# Sheet1.net
KiCad netlist of a schematic drawn in Altium Designer
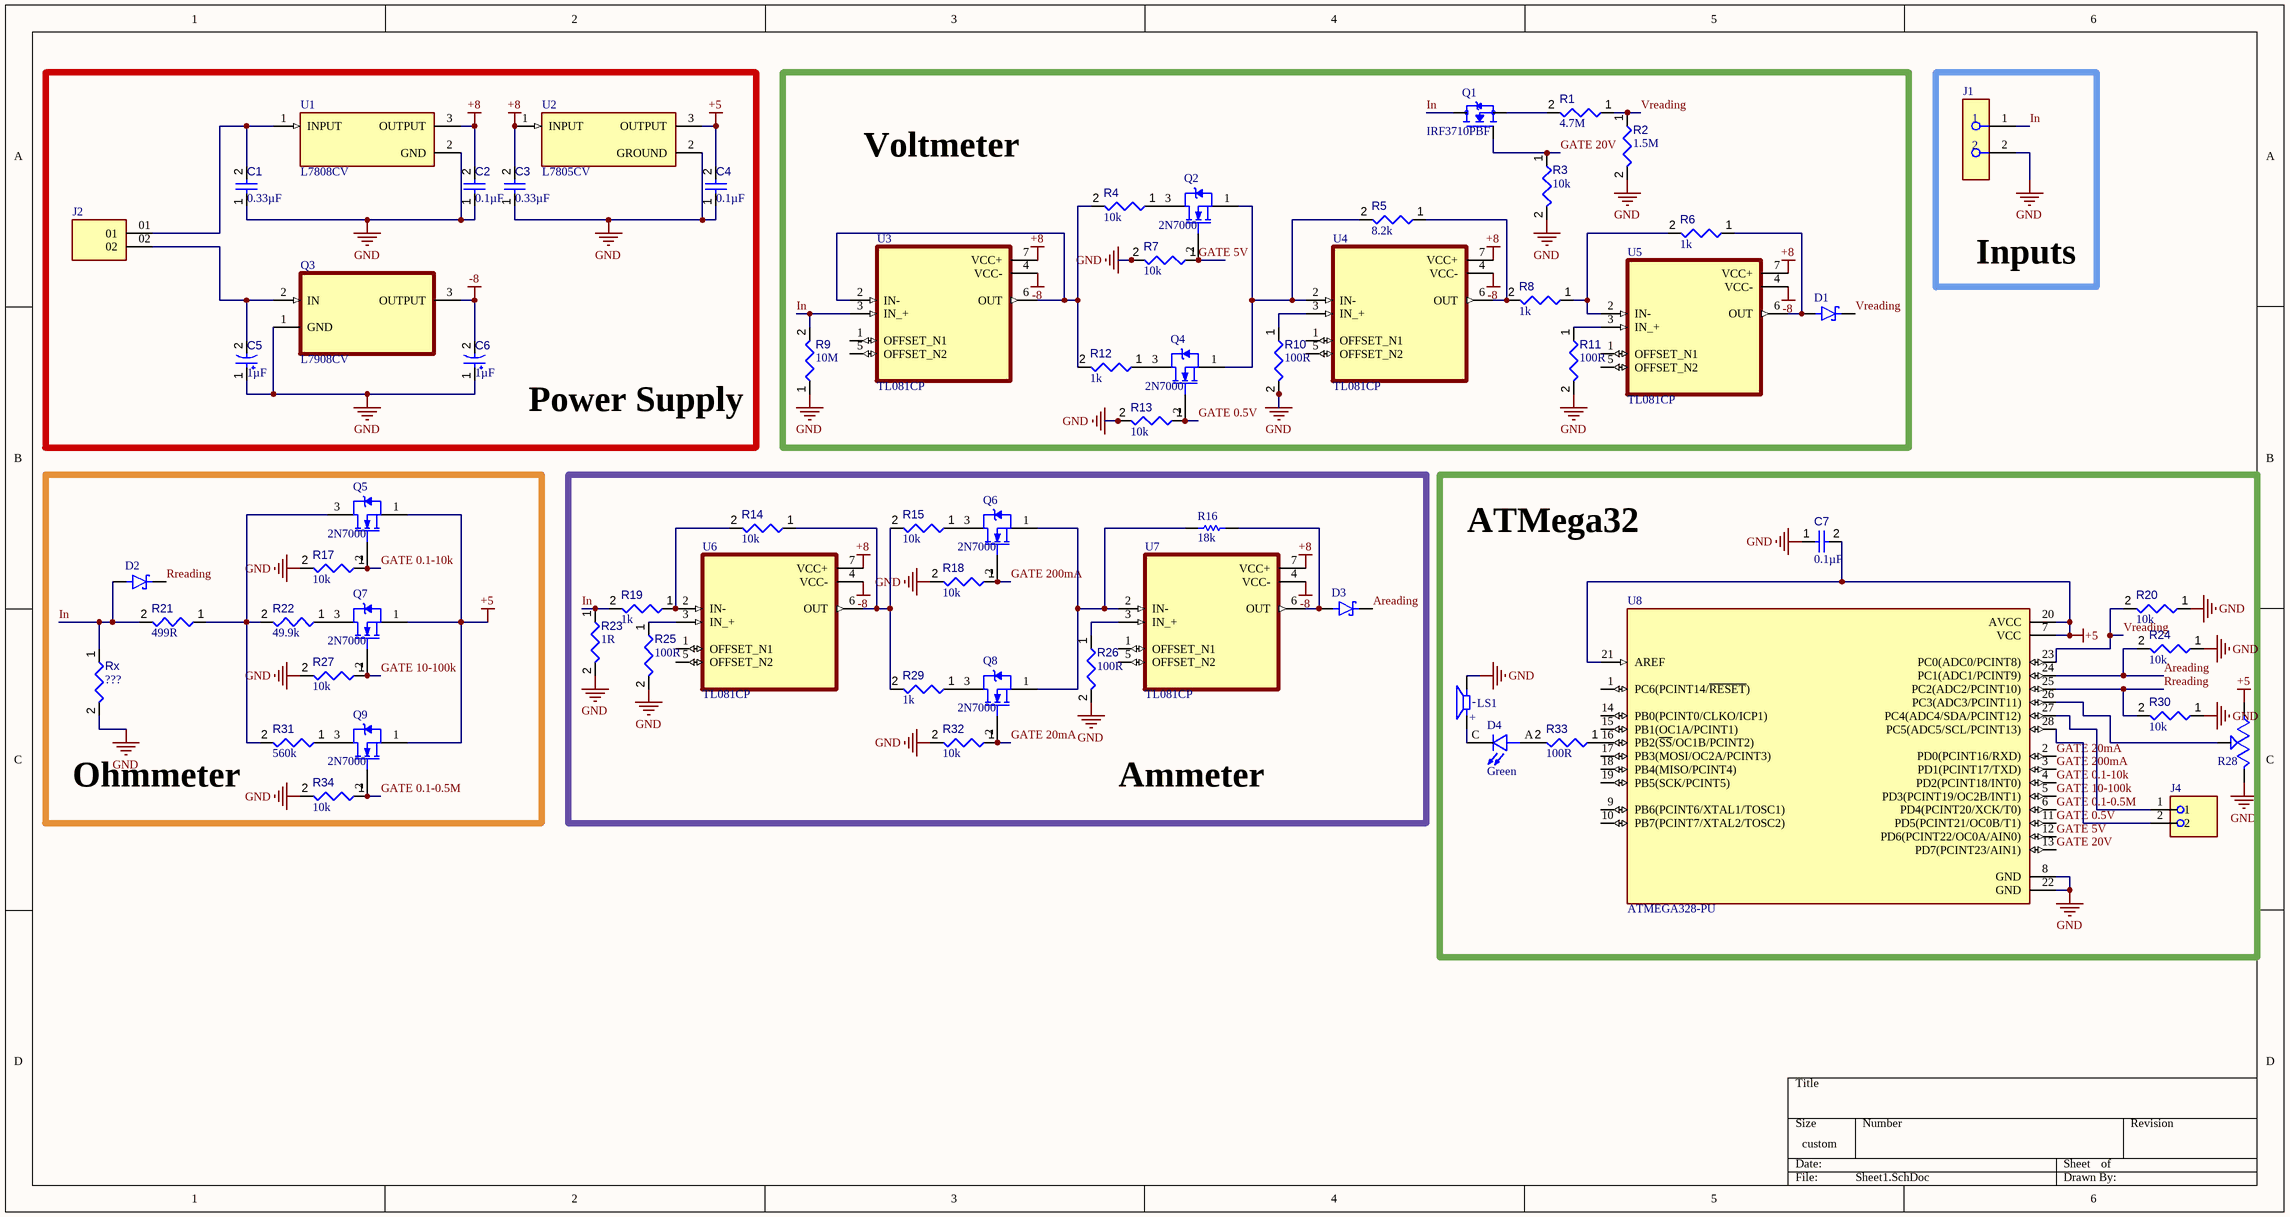
[diagram p0: Sheet1.SchDoc]

(export (version "E")
  (design (tool "Eeschema 10.0.6"))
  (components
    (comp (ref "C1")
      (value "0.33µF")
      (footprint "CAPC2013X135X45NL10T25")
      (description "Chip Capacitor, 1 uF, +/- 10%, 50 V, 0805 (2012 Metric)")
      (fields (field (name "TOLERANCE") "10%") (field (name "Comment") "Capacitor 1 uF +/- 10% 50 V 0805"))
      (libsource (lib "DMM Lab Project") (part "CAP-NP-2"))
    )
    (comp (ref "C2")
      (value "0.1µF")
      (footprint "CAPC2013X135X45NL10T25")
      (description "Chip Capacitor, 1 uF, +/- 10%, 50 V, 0805 (2012 Metric)")
      (fields (field (name "TOLERANCE") "10%") (field (name "Comment") "Capacitor 1 uF +/- 10% 50 V 0805"))
      (libsource (lib "DMM Lab Project") (part "CAP-NP-2"))
    )
    (comp (ref "C3")
      (value "0.33µF")
      (footprint "CAPC2013X135X45NL10T25")
      (description "Chip Capacitor, 1 uF, +/- 10%, 50 V, 0805 (2012 Metric)")
      (fields (field (name "TOLERANCE") "10%") (field (name "Comment") "Capacitor 1 uF +/- 10% 50 V 0805"))
      (libsource (lib "DMM Lab Project") (part "CAP-NP-2"))
    )
    (comp (ref "C4")
      (value "0.1µF")
      (footprint "CAPC2013X135X45NL10T25")
      (description "Chip Capacitor, 1 uF, +/- 10%, 50 V, 0805 (2012 Metric)")
      (fields (field (name "TOLERANCE") "10%") (field (name "Comment") "Capacitor 1 uF +/- 10% 50 V 0805"))
      (libsource (lib "DMM Lab Project") (part "CAP-NP-2"))
    )
    (comp (ref "C5")
      (value "1µF")
      (footprint "CAPPR65-350-1150X800X1250")
      (description "Aluminum Electrolytic Capacitor, 47 uF, +/- 20%, 100 V, -40 to 85 degC, 2-Pin THD, RoHS, Bulk")
      (fields (field (name "MANUFACTURER") "Panasonic") (field (name "TOLERANCE") "20%"))
      (libsource (lib "DMM Lab Project") (part "CAP-P-2"))
    )
    (comp (ref "C6")
      (value "1µF")
      (footprint "CAPPR65-350-1150X800X1250")
      (description "Aluminum Electrolytic Capacitor, 47 uF, +/- 20%, 100 V, -40 to 85 degC, 2-Pin THD, RoHS, Bulk")
      (fields (field (name "MANUFACTURER") "Panasonic") (field (name "TOLERANCE") "20%"))
      (libsource (lib "DMM Lab Project") (part "CAP-P-2"))
    )
    (comp (ref "C7")
      (value "0.1µF")
      (footprint "CAPC2013X135X45NL10T25")
      (description "Chip Capacitor, 1 uF, +/- 10%, 50 V, 0805 (2012 Metric)")
      (fields (field (name "TOLERANCE") "10%") (field (name "Comment") "Capacitor 1 uF +/- 10% 50 V 0805"))
      (libsource (lib "DMM Lab Project") (part "CAP-NP-2"))
    )
    (comp (ref "D1")
      (value "1N4733A")
      (footprint "DIOAD1036W78L463D272")
      (description "Zener Diode 5.1 V 1 W Â±5% Through Hole DO-41")
      (fields (field (name "MF") "onsemi"))
      (libsource (lib "1N4733A") (part "1N4733A"))
    )
    (comp (ref "D2")
      (value "1N4733A")
      (footprint "DIOAD1036W78L463D272")
      (description "Zener Diode 5.1 V 1 W Â±5% Through Hole DO-41")
      (fields (field (name "MF") "onsemi"))
      (libsource (lib "1N4733A") (part "1N4733A"))
    )
    (comp (ref "D3")
      (value "1N4733A")
      (footprint "DIOAD1036W78L463D272")
      (description "Zener Diode 5.1 V 1 W Â±5% Through Hole DO-41")
      (fields (field (name "MF") "onsemi"))
      (libsource (lib "1N4733A") (part "1N4733A"))
    )
    (comp (ref "D4")
      (value "Green")
      (footprint "LEDRD254W50D500H1060")
      (description "LED 5mm Green 568nm 20mcd/10mA 60Â°")
      (fields (field (name "MF") "Kingbright") (field (name "MP") "L-53GD"))
      (libsource (lib "L-53GD") (part "L-53GD"))
    )
    (comp (ref "J1")
      (value "CMP-73906-000010-1_1")
      (footprint "FP-2269-2-MFG")
      (description "CONN DBL BANANA JACK TURRET")
      (libsource (lib "DMM Lab Project") (part "CMP-73906-000010-1_1"))
    )
    (comp (ref "J2")
      (value "SSW-102-01-X-S")
      (footprint "SAMTEC_SSW-102-01-X-S")
      (description "2 Position Receptacle Connector Through Hole")
      (fields (field (name "MP") "SSW-102-01-G-S") (field (name "MF") "Samtec"))
      (libsource (lib "SSW-102-01-X-S") (part "SSW-102-01-X-S"))
    )
    (comp (ref "J4")
      (value "1713723")
      (footprint "PHOENIX_1713723")
      (fields (field (name "MF") "{'manufacturer': u'Phoenix Contact'}"))
      (libsource (lib "1713723") (part "1713723"))
    )
    (comp (ref "LS1")
      (value "PKM17EPP-2002-B0")
      (footprint "SPKR_PKM17EPP-2002-B0")
      (description "Buzzers Transducer, Externally Driven Piezo 3V 2kHz 70dB @ 3V, 10cm Through Hole PC Pins")
      (libsource (lib "PKM17EPP-2002-B0") (part "PKM17EPP-2002-B0"))
    )
    (comp (ref "Q1")
      (value "IRF3710PBF")
      (footprint "TO254P1016X419X2057-3")
      (fields (field (name "MF") "Infineon Technologies"))
      (libsource (lib "IRF3710PBF") (part "IRF3710PBF"))
    )
    (comp (ref "Q2")
      (value "2N7000")
      (footprint "ONSC-TO-92-3-29-11_AM_BL")
      (description "Small Signal MOSFET, 200 mA, 60 V, N-Channel, 3-Pin TO-92, Bulk Box")
      (fields (field (name "POWER") "400mW") (field (name "MANUFACTURER") "Fairchild Semiconductor"))
      (libsource (lib "DMM Lab Project") (part "ONSC-NMOS-S1G2D3-3"))
    )
    (comp (ref "Q3")
      (value "L7908CV")
      (footprint "TO254P450X1020X1935-3P")
      (description "Linear Voltage Regulator IC Negative Fixed 1 Output  1.5A TO-220")
      (fields (field (name "MF") "STMicroelectronics"))
      (libsource (lib "L7908CV") (part "L7908CV"))
    )
    (comp (ref "Q4")
      (value "2N7000")
      (footprint "ONSC-TO-92-3-29-11_AM_BL")
      (description "Small Signal MOSFET, 200 mA, 60 V, N-Channel, 3-Pin TO-92, Bulk Box")
      (fields (field (name "POWER") "400mW") (field (name "MANUFACTURER") "Fairchild Semiconductor"))
      (libsource (lib "DMM Lab Project") (part "ONSC-NMOS-S1G2D3-3"))
    )
    (comp (ref "Q5")
      (value "2N7000")
      (footprint "ONSC-TO-92-3-29-11_AM_BL")
      (description "Small Signal MOSFET, 200 mA, 60 V, N-Channel, 3-Pin TO-92, Bulk Box")
      (fields (field (name "POWER") "400mW") (field (name "MANUFACTURER") "Fairchild Semiconductor"))
      (libsource (lib "DMM Lab Project") (part "ONSC-NMOS-S1G2D3-3"))
    )
    (comp (ref "Q6")
      (value "2N7000")
      (footprint "ONSC-TO-92-3-29-11_AM_BL")
      (description "Small Signal MOSFET, 200 mA, 60 V, N-Channel, 3-Pin TO-92, Bulk Box")
      (fields (field (name "POWER") "400mW") (field (name "MANUFACTURER") "Fairchild Semiconductor"))
      (libsource (lib "DMM Lab Project") (part "ONSC-NMOS-S1G2D3-3"))
    )
    (comp (ref "Q7")
      (value "2N7000")
      (footprint "ONSC-TO-92-3-29-11_AM_BL")
      (description "Small Signal MOSFET, 200 mA, 60 V, N-Channel, 3-Pin TO-92, Bulk Box")
      (fields (field (name "POWER") "400mW") (field (name "MANUFACTURER") "Fairchild Semiconductor"))
      (libsource (lib "DMM Lab Project") (part "ONSC-NMOS-S1G2D3-3"))
    )
    (comp (ref "Q8")
      (value "2N7000")
      (footprint "ONSC-TO-92-3-29-11_AM_BL")
      (description "Small Signal MOSFET, 200 mA, 60 V, N-Channel, 3-Pin TO-92, Bulk Box")
      (fields (field (name "POWER") "400mW") (field (name "MANUFACTURER") "Fairchild Semiconductor"))
      (libsource (lib "DMM Lab Project") (part "ONSC-NMOS-S1G2D3-3"))
    )
    (comp (ref "Q9")
      (value "2N7000")
      (footprint "ONSC-TO-92-3-29-11_AM_BL")
      (description "Small Signal MOSFET, 200 mA, 60 V, N-Channel, 3-Pin TO-92, Bulk Box")
      (fields (field (name "POWER") "400mW") (field (name "MANUFACTURER") "Fairchild Semiconductor"))
      (libsource (lib "DMM Lab Project") (part "ONSC-NMOS-S1G2D3-3"))
    )
    (comp (ref "R1")
      (value "4.7M")
      (footprint "RESC0805(2012)_L")
      (description "1K 0.125W 5% 0805 (2012 Metric)  SMD")
      (fields (field (name "TOLERANCE") "5%") (field (name "POWER") "125mW"))
      (libsource (lib "DMM Lab Project") (part "1KR5J"))
    )
    (comp (ref "R2")
      (value "1.5M")
      (footprint "RESC0805(2012)_L")
      (description "1K 0.125W 5% 0805 (2012 Metric)  SMD")
      (fields (field (name "TOLERANCE") "5%") (field (name "POWER") "125mW"))
      (libsource (lib "DMM Lab Project") (part "1KR5J"))
    )
    (comp (ref "R3")
      (value "10k")
      (footprint "RESC0805(2012)_L")
      (description "1K 0.125W 5% 0805 (2012 Metric)  SMD")
      (fields (field (name "TOLERANCE") "5%") (field (name "POWER") "125mW"))
      (libsource (lib "DMM Lab Project") (part "1KR5J"))
    )
    (comp (ref "R4")
      (value "10k")
      (footprint "RESC0805(2012)_L")
      (description "1K 0.125W 5% 0805 (2012 Metric)  SMD")
      (fields (field (name "TOLERANCE") "5%") (field (name "POWER") "125mW"))
      (libsource (lib "DMM Lab Project") (part "1KR5J"))
    )
    (comp (ref "R5")
      (value "8.2k")
      (footprint "RESC0805(2012)_L")
      (description "1K 0.125W 5% 0805 (2012 Metric)  SMD")
      (fields (field (name "TOLERANCE") "5%") (field (name "POWER") "125mW"))
      (libsource (lib "DMM Lab Project") (part "1KR5J"))
    )
    (comp (ref "R6")
      (value "1k")
      (footprint "RESC0805(2012)_L")
      (description "1K 0.125W 5% 0805 (2012 Metric)  SMD")
      (fields (field (name "TOLERANCE") "5%") (field (name "POWER") "125mW"))
      (libsource (lib "DMM Lab Project") (part "1KR5J"))
    )
    (comp (ref "R7")
      (value "10k")
      (footprint "RESC0805(2012)_L")
      (description "1K 0.125W 5% 0805 (2012 Metric)  SMD")
      (fields (field (name "TOLERANCE") "5%") (field (name "POWER") "125mW"))
      (libsource (lib "DMM Lab Project") (part "1KR5J"))
    )
    (comp (ref "R8")
      (value "1k")
      (footprint "RESC0805(2012)_L")
      (description "1K 0.125W 5% 0805 (2012 Metric)  SMD")
      (fields (field (name "TOLERANCE") "5%") (field (name "POWER") "125mW"))
      (libsource (lib "DMM Lab Project") (part "1KR5J"))
    )
    (comp (ref "R9")
      (value "10M")
      (footprint "RESC0805(2012)_L")
      (description "1K 0.125W 5% 0805 (2012 Metric)  SMD")
      (fields (field (name "TOLERANCE") "5%") (field (name "POWER") "125mW"))
      (libsource (lib "DMM Lab Project") (part "1KR5J"))
    )
    (comp (ref "R10")
      (value "100R")
      (footprint "RESC0805(2012)_L")
      (description "1K 0.125W 5% 0805 (2012 Metric)  SMD")
      (fields (field (name "TOLERANCE") "5%") (field (name "POWER") "125mW"))
      (libsource (lib "DMM Lab Project") (part "1KR5J"))
    )
    (comp (ref "R11")
      (value "100R")
      (footprint "RESC0805(2012)_L")
      (description "1K 0.125W 5% 0805 (2012 Metric)  SMD")
      (fields (field (name "TOLERANCE") "5%") (field (name "POWER") "125mW"))
      (libsource (lib "DMM Lab Project") (part "1KR5J"))
    )
    (comp (ref "R12")
      (value "1k")
      (footprint "RESC0805(2012)_L")
      (description "1K 0.125W 5% 0805 (2012 Metric)  SMD")
      (fields (field (name "TOLERANCE") "5%") (field (name "POWER") "125mW"))
      (libsource (lib "DMM Lab Project") (part "1KR5J"))
    )
    (comp (ref "R13")
      (value "10k")
      (footprint "RESC0805(2012)_L")
      (description "1K 0.125W 5% 0805 (2012 Metric)  SMD")
      (fields (field (name "TOLERANCE") "5%") (field (name "POWER") "125mW"))
      (libsource (lib "DMM Lab Project") (part "1KR5J"))
    )
    (comp (ref "R14")
      (value "10k")
      (footprint "RESC0805(2012)_L")
      (description "1K 0.125W 5% 0805 (2012 Metric)  SMD")
      (fields (field (name "TOLERANCE") "5%") (field (name "POWER") "125mW"))
      (libsource (lib "DMM Lab Project") (part "1KR5J"))
    )
    (comp (ref "R15")
      (value "10k")
      (footprint "RESC0805(2012)_L")
      (description "1K 0.125W 5% 0805 (2012 Metric)  SMD")
      (fields (field (name "TOLERANCE") "5%") (field (name "POWER") "125mW"))
      (libsource (lib "DMM Lab Project") (part "1KR5J"))
    )
    (comp (ref "R16")
      (value "18k")
      (footprint "RESC3116X70X50ML13T20")
      (description "Chip Resistor, 1 KOhm, +/- 1%, 0.25 W, -55 to 155 degC, 1206 (3216 Metric)")
      (fields (field (name "TOLERANCE") "1%") (field (name "POWER") "250mW"))
      (libsource (lib "DMM Lab Project") (part "RES-2"))
    )
    (comp (ref "R17")
      (value "10k")
      (footprint "RESC0805(2012)_L")
      (description "1K 0.125W 5% 0805 (2012 Metric)  SMD")
      (fields (field (name "TOLERANCE") "5%") (field (name "POWER") "125mW"))
      (libsource (lib "DMM Lab Project") (part "1KR5J"))
    )
    (comp (ref "R18")
      (value "10k")
      (footprint "RESC0805(2012)_L")
      (description "1K 0.125W 5% 0805 (2012 Metric)  SMD")
      (fields (field (name "TOLERANCE") "5%") (field (name "POWER") "125mW"))
      (libsource (lib "DMM Lab Project") (part "1KR5J"))
    )
    (comp (ref "R19")
      (value "1k")
      (footprint "RESC0805(2012)_L")
      (description "1K 0.125W 5% 0805 (2012 Metric)  SMD")
      (fields (field (name "TOLERANCE") "5%") (field (name "POWER") "125mW"))
      (libsource (lib "DMM Lab Project") (part "1KR5J"))
    )
    (comp (ref "R20")
      (value "10k")
      (footprint "RESC0805(2012)_L")
      (description "1K 0.125W 5% 0805 (2012 Metric)  SMD")
      (fields (field (name "TOLERANCE") "5%") (field (name "POWER") "125mW"))
      (libsource (lib "DMM Lab Project") (part "1KR5J"))
    )
    (comp (ref "R21")
      (value "499R")
      (footprint "RESC0805(2012)_L")
      (description "1K 0.125W 5% 0805 (2012 Metric)  SMD")
      (fields (field (name "TOLERANCE") "5%") (field (name "POWER") "125mW"))
      (libsource (lib "DMM Lab Project") (part "1KR5J"))
    )
    (comp (ref "R22")
      (value "49.9k")
      (footprint "RESC0805(2012)_L")
      (description "1K 0.125W 5% 0805 (2012 Metric)  SMD")
      (fields (field (name "TOLERANCE") "5%") (field (name "POWER") "125mW"))
      (libsource (lib "DMM Lab Project") (part "1KR5J"))
    )
    (comp (ref "R23")
      (value "1R")
      (footprint "RESC0805(2012)_L")
      (description "1K 0.125W 5% 0805 (2012 Metric)  SMD")
      (fields (field (name "TOLERANCE") "5%") (field (name "POWER") "125mW"))
      (libsource (lib "DMM Lab Project") (part "1KR5J"))
    )
    (comp (ref "R24")
      (value "10k")
      (footprint "RESC0805(2012)_L")
      (description "1K 0.125W 5% 0805 (2012 Metric)  SMD")
      (fields (field (name "TOLERANCE") "5%") (field (name "POWER") "125mW"))
      (libsource (lib "DMM Lab Project") (part "1KR5J"))
    )
    (comp (ref "R25")
      (value "100R")
      (footprint "RESC0805(2012)_L")
      (description "1K 0.125W 5% 0805 (2012 Metric)  SMD")
      (fields (field (name "TOLERANCE") "5%") (field (name "POWER") "125mW"))
      (libsource (lib "DMM Lab Project") (part "1KR5J"))
    )
    (comp (ref "R26")
      (value "100R")
      (footprint "RESC0805(2012)_L")
      (description "1K 0.125W 5% 0805 (2012 Metric)  SMD")
      (fields (field (name "TOLERANCE") "5%") (field (name "POWER") "125mW"))
      (libsource (lib "DMM Lab Project") (part "1KR5J"))
    )
    (comp (ref "R27")
      (value "10k")
      (footprint "RESC0805(2012)_L")
      (description "1K 0.125W 5% 0805 (2012 Metric)  SMD")
      (fields (field (name "TOLERANCE") "5%") (field (name "POWER") "125mW"))
      (libsource (lib "DMM Lab Project") (part "1KR5J"))
    )
    (comp (ref "R28")
      (value "PTN16-A10220K1B1")
      (footprint "POT_PTN16-A10220K1B1")
      (fields (field (name "MF") "{'manufacturer': u'CUI Devices'}"))
      (libsource (lib "PTN16-A10220K1B1") (part "PTN16-A10220K1B1"))
    )
    (comp (ref "R29")
      (value "1k")
      (footprint "RESC0805(2012)_L")
      (description "1K 0.125W 5% 0805 (2012 Metric)  SMD")
      (fields (field (name "TOLERANCE") "5%") (field (name "POWER") "125mW"))
      (libsource (lib "DMM Lab Project") (part "1KR5J"))
    )
    (comp (ref "R30")
      (value "10k")
      (footprint "RESC0805(2012)_L")
      (description "1K 0.125W 5% 0805 (2012 Metric)  SMD")
      (fields (field (name "TOLERANCE") "5%") (field (name "POWER") "125mW"))
      (libsource (lib "DMM Lab Project") (part "1KR5J"))
    )
    (comp (ref "R31")
      (value "560k")
      (footprint "RESC0805(2012)_L")
      (description "1K 0.125W 5% 0805 (2012 Metric)  SMD")
      (fields (field (name "TOLERANCE") "5%") (field (name "POWER") "125mW"))
      (libsource (lib "DMM Lab Project") (part "1KR5J"))
    )
    (comp (ref "R32")
      (value "10k")
      (footprint "RESC0805(2012)_L")
      (description "1K 0.125W 5% 0805 (2012 Metric)  SMD")
      (fields (field (name "TOLERANCE") "5%") (field (name "POWER") "125mW"))
      (libsource (lib "DMM Lab Project") (part "1KR5J"))
    )
    (comp (ref "R33")
      (value "100R")
      (footprint "RESC0805(2012)_L")
      (description "1K 0.125W 5% 0805 (2012 Metric)  SMD")
      (fields (field (name "TOLERANCE") "5%") (field (name "POWER") "125mW"))
      (libsource (lib "DMM Lab Project") (part "1KR5J"))
    )
    (comp (ref "R34")
      (value "10k")
      (footprint "RESC0805(2012)_L")
      (description "1K 0.125W 5% 0805 (2012 Metric)  SMD")
      (fields (field (name "TOLERANCE") "5%") (field (name "POWER") "125mW"))
      (libsource (lib "DMM Lab Project") (part "1KR5J"))
    )
    (comp (ref "Rx")
      (value "???")
      (footprint "RESC0805(2012)_L")
      (description "1K 0.125W 5% 0805 (2012 Metric)  SMD")
      (fields (field (name "TOLERANCE") "5%") (field (name "POWER") "125mW"))
      (libsource (lib "DMM Lab Project") (part "1KR5J"))
    )
    (comp (ref "U1")
      (value "L7808CV")
      (footprint "TO255P1020X450X1968-3B")
      (description "Linear Voltage Regulator IC Positive Fixed 1 Output 1.5A TO-220")
      (fields (field (name "MF") "STMicroelectronics"))
      (libsource (lib "L7808CV") (part "L7808CV"))
    )
    (comp (ref "U2")
      (value "L7805CV")
      (footprint "TO255P1040X460X1968-3")
      (description "Linear Voltage Regulator IC Positive Fixed 1 Output 1.5A TO-220")
      (fields (field (name "MF") "STMicroelectronics"))
      (libsource (lib "L7805CV") (part "L7805CV"))
    )
    (comp (ref "U3")
      (value "TL081CP")
      (footprint "DIP794W45P254L959H508Q8")
      (description "Single, 30-V, 3-MHz, 13-V/Âµs slew rate, In to V+, JFET-input op amp")
      (fields (field (name "MF") "Texas Instruments"))
      (libsource (lib "TL081CP") (part "TL081CP"))
    )
    (comp (ref "U4")
      (value "TL081CP")
      (footprint "DIP794W45P254L959H508Q8")
      (description "Single, 30-V, 3-MHz, 13-V/Âµs slew rate, In to V+, JFET-input op amp")
      (fields (field (name "MF") "Texas Instruments"))
      (libsource (lib "TL081CP") (part "TL081CP"))
    )
    (comp (ref "U5")
      (value "TL081CP")
      (footprint "DIP794W45P254L959H508Q8")
      (description "Single, 30-V, 3-MHz, 13-V/Âµs slew rate, In to V+, JFET-input op amp")
      (fields (field (name "MF") "Texas Instruments"))
      (libsource (lib "TL081CP") (part "TL081CP"))
    )
    (comp (ref "U6")
      (value "TL081CP")
      (footprint "DIP794W45P254L959H508Q8")
      (description "Single, 30-V, 3-MHz, 13-V/Âµs slew rate, In to V+, JFET-input op amp")
      (fields (field (name "MF") "Texas Instruments"))
      (libsource (lib "TL081CP") (part "TL081CP"))
    )
    (comp (ref "U7")
      (value "TL081CP")
      (footprint "DIP794W45P254L959H508Q8")
      (description "Single, 30-V, 3-MHz, 13-V/Âµs slew rate, In to V+, JFET-input op amp")
      (fields (field (name "MF") "Texas Instruments"))
      (libsource (lib "TL081CP") (part "TL081CP"))
    )
    (comp (ref "U8")
      (value "ATMEGA328-PU")
      (footprint "DIP787W46P254L3467H508Q28")
      (description "AVR AVRÂ® ATmega Microcontroller IC 8-Bit 20MHz 32KB (16K x 16) FLASH 28-PDIP")
      (fields (field (name "MF") "Microchip"))
      (libsource (lib "ATMEGA328-PU") (part "ATMEGA328-PU"))
    )
  )
  (nets
    (net (code "1") (name "+5") (class "Default")
      (node (ref "C4") (pin "2") (pinfunction "2_2") (pintype "passive"))
      (node (ref "C7") (pin "2") (pinfunction "2_2") (pintype "passive"))
      (node (ref "Q5") (pin "1") (pinfunction "S_1") (pintype "passive"))
      (node (ref "Q7") (pin "1") (pinfunction "S_1") (pintype "passive"))
      (node (ref "Q9") (pin "1") (pinfunction "S_1") (pintype "passive"))
      (node (ref "R28") (pin "1") (pinfunction "1_1") (pintype "passive"))
      (node (ref "U2") (pin "3") (pinfunction "OUTPUT_3") (pintype "power_in"))
      (node (ref "U8") (pin "20") (pinfunction "AVCC_20") (pintype "power_in"))
      (node (ref "U8") (pin "21") (pinfunction "AREF_21") (pintype "input"))
      (node (ref "U8") (pin "7") (pinfunction "VCC_7") (pintype "power_in"))
    )
    (net (code "2") (name "+8") (class "Default")
      (node (ref "C2") (pin "2") (pinfunction "2_2") (pintype "passive"))
      (node (ref "C3") (pin "2") (pinfunction "2_2") (pintype "passive"))
      (node (ref "U1") (pin "3") (pinfunction "OUTPUT_3") (pintype "power_in"))
      (node (ref "U2") (pin "1") (pinfunction "INPUT_1") (pintype "input"))
      (node (ref "U3") (pin "7") (pinfunction "VCC+_7") (pintype "power_in"))
      (node (ref "U4") (pin "7") (pinfunction "VCC+_7") (pintype "power_in"))
      (node (ref "U5") (pin "7") (pinfunction "VCC+_7") (pintype "power_in"))
      (node (ref "U6") (pin "7") (pinfunction "VCC+_7") (pintype "power_in"))
      (node (ref "U7") (pin "7") (pinfunction "VCC+_7") (pintype "power_in"))
    )
    (net (code "3") (name "-8") (class "Default")
      (node (ref "C6") (pin "2") (pinfunction "2_2") (pintype "passive"))
      (node (ref "Q3") (pin "3") (pinfunction "OUTPUT_3") (pintype "power_in"))
      (node (ref "U3") (pin "4") (pinfunction "VCC-_4") (pintype "power_in"))
      (node (ref "U4") (pin "4") (pinfunction "VCC-_4") (pintype "power_in"))
      (node (ref "U5") (pin "4") (pinfunction "VCC-_4") (pintype "power_in"))
      (node (ref "U6") (pin "4") (pinfunction "VCC-_4") (pintype "power_in"))
      (node (ref "U7") (pin "4") (pinfunction "VCC-_4") (pintype "power_in"))
    )
    (net (code "4") (name "/Areading") (class "Default")
      (node (ref "D3") (pin "1") (pinfunction "K_1") (pintype "passive"))
      (node (ref "R24") (pin "2") (pinfunction "2_2") (pintype "passive"))
      (node (ref "U8") (pin "24") (pinfunction "PC1(ADC1/PCINT9)_24") (pintype "bidirectional"))
    )
    (net (code "5") (name "/GATE 0.1-0.5M") (class "Default")
      (node (ref "Q9") (pin "2") (pinfunction "G_2") (pintype "passive"))
      (node (ref "R34") (pin "1") (pinfunction "1_1") (pintype "passive"))
      (node (ref "U8") (pin "6") (pinfunction "PD4(PCINT20/XCK/T0)_6") (pintype "bidirectional"))
    )
    (net (code "6") (name "/GATE 0.1-10k") (class "Default")
      (node (ref "Q5") (pin "2") (pinfunction "G_2") (pintype "passive"))
      (node (ref "R17") (pin "1") (pinfunction "1_1") (pintype "passive"))
      (node (ref "U8") (pin "4") (pinfunction "PD2(PCINT18/INT0)_4") (pintype "bidirectional"))
    )
    (net (code "7") (name "/GATE 0.5V") (class "Default")
      (node (ref "Q4") (pin "2") (pinfunction "G_2") (pintype "passive"))
      (node (ref "R13") (pin "1") (pinfunction "1_1") (pintype "passive"))
      (node (ref "U8") (pin "11") (pinfunction "PD5(PCINT21/OC0B/T1)_11") (pintype "bidirectional"))
    )
    (net (code "8") (name "/GATE 5V") (class "Default")
      (node (ref "Q2") (pin "2") (pinfunction "G_2") (pintype "passive"))
      (node (ref "R7") (pin "1") (pinfunction "1_1") (pintype "passive"))
      (node (ref "U8") (pin "12") (pinfunction "PD6(PCINT22/OC0A/AIN0)_12") (pintype "bidirectional"))
    )
    (net (code "9") (name "/GATE 10-100k") (class "Default")
      (node (ref "Q7") (pin "2") (pinfunction "G_2") (pintype "passive"))
      (node (ref "R27") (pin "1") (pinfunction "1_1") (pintype "passive"))
      (node (ref "U8") (pin "5") (pinfunction "PD3(PCINT19/OC2B/INT1)_5") (pintype "bidirectional"))
    )
    (net (code "10") (name "/GATE 20V") (class "Default")
      (node (ref "Q1") (pin "1") (pinfunction "G_1") (pintype "passive"))
      (node (ref "R3") (pin "1") (pinfunction "1_1") (pintype "passive"))
      (node (ref "U8") (pin "13") (pinfunction "PD7(PCINT23/AIN1)_13") (pintype "bidirectional"))
    )
    (net (code "11") (name "/GATE 20mA") (class "Default")
      (node (ref "Q8") (pin "2") (pinfunction "G_2") (pintype "passive"))
      (node (ref "R32") (pin "1") (pinfunction "1_1") (pintype "passive"))
      (node (ref "U8") (pin "2") (pinfunction "PD0(PCINT16/RXD)_2") (pintype "bidirectional"))
    )
    (net (code "12") (name "/GATE 200mA") (class "Default")
      (node (ref "Q6") (pin "2") (pinfunction "G_2") (pintype "passive"))
      (node (ref "R18") (pin "1") (pinfunction "1_1") (pintype "passive"))
      (node (ref "U8") (pin "3") (pinfunction "PD1(PCINT17/TXD)_3") (pintype "bidirectional"))
    )
    (net (code "13") (name "/In") (class "Default")
      (node (ref "D2") (pin "2") (pinfunction "A_2") (pintype "passive"))
      (node (ref "J1") (pin "1") (pinfunction "1_1") (pintype "passive"))
      (node (ref "Q1") (pin "2") (pinfunction "D_2") (pintype "passive"))
      (node (ref "R19") (pin "2") (pinfunction "2_2") (pintype "passive"))
      (node (ref "R21") (pin "2") (pinfunction "2_2") (pintype "passive"))
      (node (ref "R23") (pin "1") (pinfunction "1_1") (pintype "passive"))
      (node (ref "R9") (pin "2") (pinfunction "2_2") (pintype "passive"))
      (node (ref "Rx") (pin "1") (pinfunction "1_1") (pintype "passive"))
      (node (ref "U3") (pin "3") (pinfunction "IN_+_3") (pintype "input"))
    )
    (net (code "14") (name "/Rreading") (class "Default")
      (node (ref "D2") (pin "1") (pinfunction "K_1") (pintype "passive"))
      (node (ref "R30") (pin "2") (pinfunction "2_2") (pintype "passive"))
      (node (ref "U8") (pin "25") (pinfunction "PC2(ADC2/PCINT10)_25") (pintype "bidirectional"))
    )
    (net (code "15") (name "/Vreading") (class "Default")
      (node (ref "D1") (pin "1") (pinfunction "K_1") (pintype "passive"))
      (node (ref "R1") (pin "1") (pinfunction "1_1") (pintype "passive"))
      (node (ref "R2") (pin "1") (pinfunction "1_1") (pintype "passive"))
      (node (ref "R20") (pin "2") (pinfunction "2_2") (pintype "passive"))
      (node (ref "U8") (pin "23") (pinfunction "PC0(ADC0/PCINT8)_23") (pintype "bidirectional"))
    )
    (net (code "16") (name "GND") (class "Default")
      (node (ref "C1") (pin "1") (pinfunction "1_1") (pintype "passive"))
      (node (ref "C2") (pin "1") (pinfunction "1_1") (pintype "passive"))
      (node (ref "C3") (pin "1") (pinfunction "1_1") (pintype "passive"))
      (node (ref "C4") (pin "1") (pinfunction "1_1") (pintype "passive"))
      (node (ref "C5") (pin "1") (pinfunction "1_1") (pintype "passive"))
      (node (ref "C6") (pin "1") (pinfunction "1_1") (pintype "passive"))
      (node (ref "C7") (pin "1") (pinfunction "1_1") (pintype "passive"))
      (node (ref "J1") (pin "2") (pinfunction "2_2") (pintype "passive"))
      (node (ref "LS1") (pin "N") (pinfunction "N_N") (pintype "passive"))
      (node (ref "Q3") (pin "1") (pinfunction "GND_1") (pintype "power_in"))
      (node (ref "R10") (pin "2") (pinfunction "2_2") (pintype "passive"))
      (node (ref "R11") (pin "2") (pinfunction "2_2") (pintype "passive"))
      (node (ref "R13") (pin "2") (pinfunction "2_2") (pintype "passive"))
      (node (ref "R17") (pin "2") (pinfunction "2_2") (pintype "passive"))
      (node (ref "R18") (pin "2") (pinfunction "2_2") (pintype "passive"))
      (node (ref "R2") (pin "2") (pinfunction "2_2") (pintype "passive"))
      (node (ref "R20") (pin "1") (pinfunction "1_1") (pintype "passive"))
      (node (ref "R23") (pin "2") (pinfunction "2_2") (pintype "passive"))
      (node (ref "R24") (pin "1") (pinfunction "1_1") (pintype "passive"))
      (node (ref "R25") (pin "2") (pinfunction "2_2") (pintype "passive"))
      (node (ref "R26") (pin "2") (pinfunction "2_2") (pintype "passive"))
      (node (ref "R27") (pin "2") (pinfunction "2_2") (pintype "passive"))
      (node (ref "R28") (pin "3") (pinfunction "3_3") (pintype "passive"))
      (node (ref "R3") (pin "2") (pinfunction "2_2") (pintype "passive"))
      (node (ref "R30") (pin "1") (pinfunction "1_1") (pintype "passive"))
      (node (ref "R32") (pin "2") (pinfunction "2_2") (pintype "passive"))
      (node (ref "R34") (pin "2") (pinfunction "2_2") (pintype "passive"))
      (node (ref "R7") (pin "2") (pinfunction "2_2") (pintype "passive"))
      (node (ref "R9") (pin "1") (pinfunction "1_1") (pintype "passive"))
      (node (ref "Rx") (pin "2") (pinfunction "2_2") (pintype "passive"))
      (node (ref "U1") (pin "2") (pinfunction "GND_2") (pintype "power_in"))
      (node (ref "U2") (pin "2") (pinfunction "GROUND_2") (pintype "power_in"))
      (node (ref "U8") (pin "22") (pinfunction "GND_22") (pintype "power_in"))
      (node (ref "U8") (pin "8") (pinfunction "GND_8") (pintype "power_in"))
    )
    (net (code "17") (name "Net-(D1-A)") (class "Default")
      (node (ref "D1") (pin "2") (pinfunction "A_2") (pintype "passive"))
      (node (ref "R6") (pin "1") (pinfunction "1_1") (pintype "passive"))
      (node (ref "U5") (pin "6") (pinfunction "OUT_6") (pintype "output"))
    )
    (net (code "18") (name "Net-(D3-A)") (class "Default")
      (node (ref "D3") (pin "2") (pinfunction "A_2") (pintype "passive"))
      (node (ref "R16") (pin "1") (pinfunction "1_1") (pintype "passive"))
      (node (ref "U7") (pin "6") (pinfunction "OUT_6") (pintype "output"))
    )
    (net (code "19") (name "Net-(D4-PadA)") (class "Default")
      (node (ref "D4") (pin "A") (pinfunction "A_A") (pintype "passive"))
      (node (ref "R33") (pin "2") (pinfunction "2_2") (pintype "passive"))
    )
    (net (code "20") (name "Net-(D4-PadC)") (class "Default")
      (node (ref "D4") (pin "C") (pinfunction "C_C") (pintype "passive"))
      (node (ref "LS1") (pin "P") (pinfunction "P_P") (pintype "passive"))
    )
    (net (code "21") (name "Net-(Q1-S)") (class "Default")
      (node (ref "Q1") (pin "3") (pinfunction "S_3") (pintype "passive"))
      (node (ref "R1") (pin "2") (pinfunction "2_2") (pintype "passive"))
    )
    (net (code "22") (name "Net-(Q2-D)") (class "Default")
      (node (ref "Q2") (pin "3") (pinfunction "D_3") (pintype "passive"))
      (node (ref "R4") (pin "1") (pinfunction "1_1") (pintype "passive"))
    )
    (net (code "23") (name "Net-(Q2-S)") (class "Default")
      (node (ref "Q2") (pin "1") (pinfunction "S_1") (pintype "passive"))
      (node (ref "Q4") (pin "1") (pinfunction "S_1") (pintype "passive"))
      (node (ref "R5") (pin "2") (pinfunction "2_2") (pintype "passive"))
      (node (ref "U4") (pin "2") (pinfunction "IN-_2") (pintype "input"))
    )
    (net (code "24") (name "Net-(Q3-IN)") (class "Default")
      (node (ref "C5") (pin "2") (pinfunction "2_2") (pintype "passive"))
      (node (ref "J2") (pin "02") (pinfunction "02_02") (pintype "passive"))
      (node (ref "Q3") (pin "2") (pinfunction "IN_2") (pintype "input"))
    )
    (net (code "25") (name "Net-(Q4-D)") (class "Default")
      (node (ref "Q4") (pin "3") (pinfunction "D_3") (pintype "passive"))
      (node (ref "R12") (pin "1") (pinfunction "1_1") (pintype "passive"))
    )
    (net (code "26") (name "Net-(Q5-D)") (class "Default")
      (node (ref "Q5") (pin "3") (pinfunction "D_3") (pintype "passive"))
      (node (ref "R21") (pin "1") (pinfunction "1_1") (pintype "passive"))
      (node (ref "R22") (pin "2") (pinfunction "2_2") (pintype "passive"))
      (node (ref "R31") (pin "2") (pinfunction "2_2") (pintype "passive"))
    )
    (net (code "27") (name "Net-(Q6-D)") (class "Default")
      (node (ref "Q6") (pin "3") (pinfunction "D_3") (pintype "passive"))
      (node (ref "R15") (pin "1") (pinfunction "1_1") (pintype "passive"))
    )
    (net (code "28") (name "Net-(Q6-S)") (class "Default")
      (node (ref "Q6") (pin "1") (pinfunction "S_1") (pintype "passive"))
      (node (ref "Q8") (pin "1") (pinfunction "S_1") (pintype "passive"))
      (node (ref "R16") (pin "2") (pinfunction "2_2") (pintype "passive"))
      (node (ref "U7") (pin "2") (pinfunction "IN-_2") (pintype "input"))
    )
    (net (code "29") (name "Net-(Q7-D)") (class "Default")
      (node (ref "Q7") (pin "3") (pinfunction "D_3") (pintype "passive"))
      (node (ref "R22") (pin "1") (pinfunction "1_1") (pintype "passive"))
    )
    (net (code "30") (name "Net-(Q8-D)") (class "Default")
      (node (ref "Q8") (pin "3") (pinfunction "D_3") (pintype "passive"))
      (node (ref "R29") (pin "1") (pinfunction "1_1") (pintype "passive"))
    )
    (net (code "31") (name "Net-(Q9-D)") (class "Default")
      (node (ref "Q9") (pin "3") (pinfunction "D_3") (pintype "passive"))
      (node (ref "R31") (pin "1") (pinfunction "1_1") (pintype "passive"))
    )
    (net (code "32") (name "Net-(U1-INPUT)") (class "Default")
      (node (ref "C1") (pin "2") (pinfunction "2_2") (pintype "passive"))
      (node (ref "J2") (pin "01") (pinfunction "01_01") (pintype "passive"))
      (node (ref "U1") (pin "1") (pinfunction "INPUT_1") (pintype "input"))
    )
    (net (code "33") (name "Net-(U3-IN-)") (class "Default")
      (node (ref "R12") (pin "2") (pinfunction "2_2") (pintype "passive"))
      (node (ref "R4") (pin "2") (pinfunction "2_2") (pintype "passive"))
      (node (ref "U3") (pin "2") (pinfunction "IN-_2") (pintype "input"))
      (node (ref "U3") (pin "6") (pinfunction "OUT_6") (pintype "output"))
    )
    (net (code "34") (name "Net-(U4-IN_+)") (class "Default")
      (node (ref "R10") (pin "1") (pinfunction "1_1") (pintype "passive"))
      (node (ref "U4") (pin "3") (pinfunction "IN_+_3") (pintype "input"))
    )
    (net (code "35") (name "Net-(U4-OUT)") (class "Default")
      (node (ref "R5") (pin "1") (pinfunction "1_1") (pintype "passive"))
      (node (ref "R8") (pin "2") (pinfunction "2_2") (pintype "passive"))
      (node (ref "U4") (pin "6") (pinfunction "OUT_6") (pintype "output"))
    )
    (net (code "36") (name "Net-(U5-IN-)") (class "Default")
      (node (ref "R6") (pin "2") (pinfunction "2_2") (pintype "passive"))
      (node (ref "R8") (pin "1") (pinfunction "1_1") (pintype "passive"))
      (node (ref "U5") (pin "2") (pinfunction "IN-_2") (pintype "input"))
    )
    (net (code "37") (name "Net-(U5-IN_+)") (class "Default")
      (node (ref "R11") (pin "1") (pinfunction "1_1") (pintype "passive"))
      (node (ref "U5") (pin "3") (pinfunction "IN_+_3") (pintype "input"))
    )
    (net (code "38") (name "Net-(U6-IN-)") (class "Default")
      (node (ref "R14") (pin "2") (pinfunction "2_2") (pintype "passive"))
      (node (ref "R19") (pin "1") (pinfunction "1_1") (pintype "passive"))
      (node (ref "U6") (pin "2") (pinfunction "IN-_2") (pintype "input"))
    )
    (net (code "39") (name "Net-(U6-IN_+)") (class "Default")
      (node (ref "R25") (pin "1") (pinfunction "1_1") (pintype "passive"))
      (node (ref "U6") (pin "3") (pinfunction "IN_+_3") (pintype "input"))
    )
    (net (code "40") (name "Net-(U6-OUT)") (class "Default")
      (node (ref "R14") (pin "1") (pinfunction "1_1") (pintype "passive"))
      (node (ref "R15") (pin "2") (pinfunction "2_2") (pintype "passive"))
      (node (ref "R29") (pin "2") (pinfunction "2_2") (pintype "passive"))
      (node (ref "U6") (pin "6") (pinfunction "OUT_6") (pintype "output"))
    )
    (net (code "41") (name "Net-(U7-IN_+)") (class "Default")
      (node (ref "R26") (pin "1") (pinfunction "1_1") (pintype "passive"))
      (node (ref "U7") (pin "3") (pinfunction "IN_+_3") (pintype "input"))
    )
    (net (code "42") (name "Net-(U8-PB2(~{SS}{slash}OC1B{slash}PCINT2))") (class "Default")
      (node (ref "R33") (pin "1") (pinfunction "1_1") (pintype "passive"))
      (node (ref "U8") (pin "16") (pinfunction "PB2(~{SS}/OC1B/PCINT2)_16") (pintype "bidirectional"))
    )
    (net (code "43") (name "Net-(U8-PC3(ADC3{slash}PCINT11))") (class "Default")
      (node (ref "R28") (pin "2") (pinfunction "2_2") (pintype "passive"))
      (node (ref "U8") (pin "26") (pinfunction "PC3(ADC3/PCINT11)_26") (pintype "bidirectional"))
    )
    (net (code "44") (name "Net-(U8-PC4(ADC4{slash}SDA{slash}PCINT12))") (class "Default")
      (node (ref "J4") (pin "1") (pinfunction "1_1") (pintype "passive"))
      (node (ref "U8") (pin "27") (pinfunction "PC4(ADC4/SDA/PCINT12)_27") (pintype "bidirectional"))
    )
    (net (code "45") (name "Net-(U8-PC5(ADC5{slash}SCL{slash}PCINT13))") (class "Default")
      (node (ref "J4") (pin "2") (pinfunction "2_2") (pintype "passive"))
      (node (ref "U8") (pin "28") (pinfunction "PC5(ADC5/SCL/PCINT13)_28") (pintype "bidirectional"))
    )
    (net (code "46") (name "unconnected-(U3-OFFSET_N1-Pad1)") (class "Default")
      (node (ref "U3") (pin "1") (pinfunction "OFFSET_N1_1") (pintype "bidirectional"))
    )
    (net (code "47") (name "unconnected-(U3-OFFSET_N2-Pad5)") (class "Default")
      (node (ref "U3") (pin "5") (pinfunction "OFFSET_N2_5") (pintype "bidirectional"))
    )
    (net (code "48") (name "unconnected-(U4-OFFSET_N1-Pad1)") (class "Default")
      (node (ref "U4") (pin "1") (pinfunction "OFFSET_N1_1") (pintype "bidirectional"))
    )
    (net (code "49") (name "unconnected-(U4-OFFSET_N2-Pad5)") (class "Default")
      (node (ref "U4") (pin "5") (pinfunction "OFFSET_N2_5") (pintype "bidirectional"))
    )
    (net (code "50") (name "unconnected-(U5-OFFSET_N1-Pad1)") (class "Default")
      (node (ref "U5") (pin "1") (pinfunction "OFFSET_N1_1") (pintype "bidirectional"))
    )
    (net (code "51") (name "unconnected-(U5-OFFSET_N2-Pad5)") (class "Default")
      (node (ref "U5") (pin "5") (pinfunction "OFFSET_N2_5") (pintype "bidirectional"))
    )
    (net (code "52") (name "unconnected-(U6-OFFSET_N1-Pad1)") (class "Default")
      (node (ref "U6") (pin "1") (pinfunction "OFFSET_N1_1") (pintype "bidirectional"))
    )
    (net (code "53") (name "unconnected-(U6-OFFSET_N2-Pad5)") (class "Default")
      (node (ref "U6") (pin "5") (pinfunction "OFFSET_N2_5") (pintype "bidirectional"))
    )
    (net (code "54") (name "unconnected-(U7-OFFSET_N1-Pad1)") (class "Default")
      (node (ref "U7") (pin "1") (pinfunction "OFFSET_N1_1") (pintype "bidirectional"))
    )
    (net (code "55") (name "unconnected-(U7-OFFSET_N2-Pad5)") (class "Default")
      (node (ref "U7") (pin "5") (pinfunction "OFFSET_N2_5") (pintype "bidirectional"))
    )
    (net (code "56") (name "unconnected-(U8-PB0(PCINT0{slash}CLKO{slash}ICP1)-Pad14)") (class "Default")
      (node (ref "U8") (pin "14") (pinfunction "PB0(PCINT0/CLKO/ICP1)_14") (pintype "bidirectional"))
    )
    (net (code "57") (name "unconnected-(U8-PB1(OC1A{slash}PCINT1)-Pad15)") (class "Default")
      (node (ref "U8") (pin "15") (pinfunction "PB1(OC1A/PCINT1)_15") (pintype "bidirectional"))
    )
    (net (code "58") (name "unconnected-(U8-PB3(MOSI{slash}OC2A{slash}PCINT3)-Pad17)") (class "Default")
      (node (ref "U8") (pin "17") (pinfunction "PB3(MOSI/OC2A/PCINT3)_17") (pintype "bidirectional"))
    )
    (net (code "59") (name "unconnected-(U8-PB4(MISO{slash}PCINT4)-Pad18)") (class "Default")
      (node (ref "U8") (pin "18") (pinfunction "PB4(MISO/PCINT4)_18") (pintype "bidirectional"))
    )
    (net (code "60") (name "unconnected-(U8-PB5(SCK{slash}PCINT5)-Pad19)") (class "Default")
      (node (ref "U8") (pin "19") (pinfunction "PB5(SCK/PCINT5)_19") (pintype "bidirectional"))
    )
    (net (code "61") (name "unconnected-(U8-PB6(PCINT6{slash}XTAL1{slash}TOSC1)-Pad9)") (class "Default")
      (node (ref "U8") (pin "9") (pinfunction "PB6(PCINT6/XTAL1/TOSC1)_9") (pintype "bidirectional"))
    )
    (net (code "62") (name "unconnected-(U8-PB7(PCINT7{slash}XTAL2{slash}TOSC2)-Pad10)") (class "Default")
      (node (ref "U8") (pin "10") (pinfunction "PB7(PCINT7/XTAL2/TOSC2)_10") (pintype "bidirectional"))
    )
    (net (code "63") (name "unconnected-(U8-PC6(PCINT14{slash}~{RESET})-Pad1)") (class "Default")
      (node (ref "U8") (pin "1") (pinfunction "PC6(PCINT14/~{RESET})_1") (pintype "bidirectional"))
    )
  )
)
